# SCH_Stimulus-Shield-_GroeiAcademie-Frame.net
KiCad netlist of a schematic drawn in EasyEDA
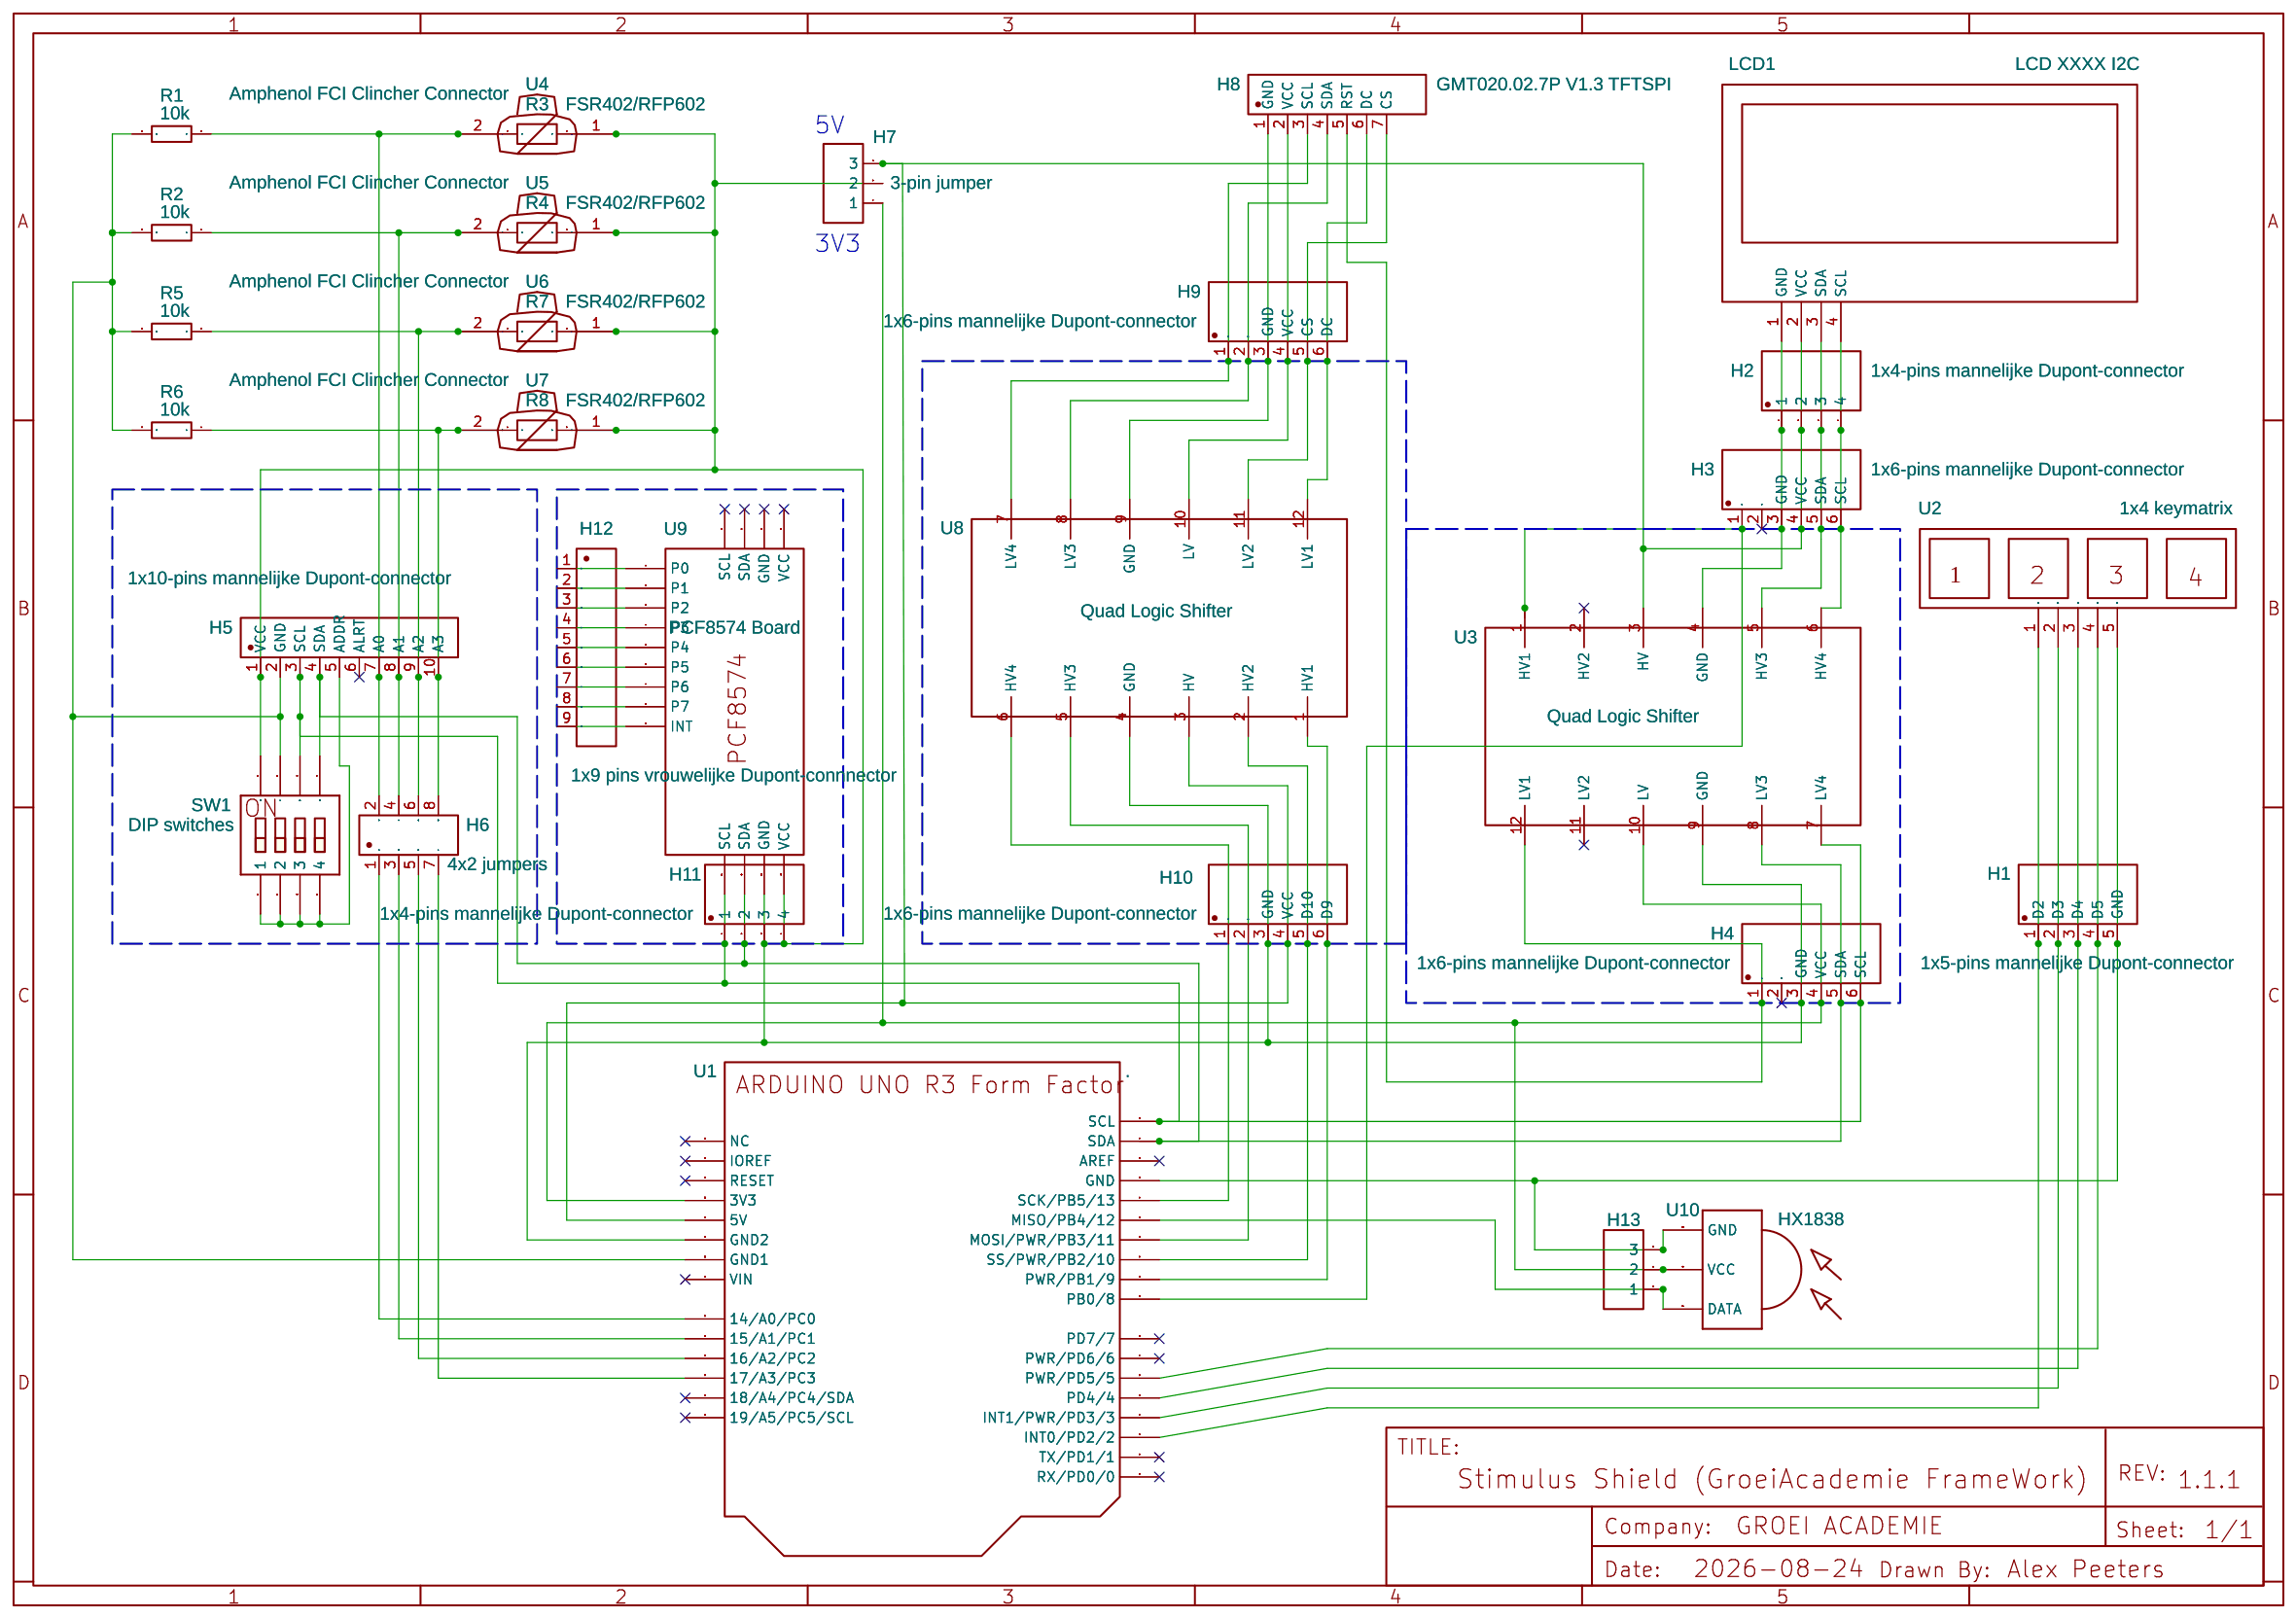
[diagram p0: schematic sheet]

(export (version "E")
  (design (tool "Eeschema 10.0.6"))
  (components
    (comp (ref "H1")
      (value "1x5-pins mannelijke Dupont-connector")
      (fields (field (name "Manufacturer Part") "B-2100S05P-A110") (field (name "Manufacturer") "Ckmtw(灿科盟)"))
      (libsource (lib "") (part "210S-1*5P L=11.6MMGold-plated black"))
    )
    (comp (ref "H2")
      (value "1x4-pins mannelijke Dupont-connector")
      (fields (field (name "Manufacturer Part") "B-2100S04P-A110") (field (name "Manufacturer") "Ckmtw(灿科盟)"))
      (libsource (lib "") (part "Header-Male-2.54_1x4"))
    )
    (comp (ref "H3")
      (value "1x6-pins mannelijke Dupont-connector")
      (fields (field (name "Manufacturer Part") "B-2100S06P-A110") (field (name "Manufacturer") "Ckmtw(灿科盟)"))
      (libsource (lib "") (part "210S-1*6P L=11.6MMGold-plated black"))
    )
    (comp (ref "H4")
      (value "1x6-pins mannelijke Dupont-connector")
      (fields (field (name "Manufacturer Part") "B-2100S06P-A110") (field (name "Manufacturer") "Ckmtw(灿科盟)"))
      (libsource (lib "") (part "210S-1*6P L=11.6MMGold-plated black"))
    )
    (comp (ref "H5")
      (value "1x10-pins mannelijke Dupont-connector")
      (fields (field (name "Manufacturer Part") "2.54-1*10") (field (name "Manufacturer") "ZHOURI(洲日)"))
      (libsource (lib "") (part "2.54-1*10"))
    )
    (comp (ref "H6")
      (value "4x2 jumpers")
      (fields (field (name "Manufacturer Part") "2.54-2*4P立贴针") (field (name "Manufacturer") "BOOMELE(博穆精密)"))
      (libsource (lib "") (part "2.54-2*4P立贴针"))
    )
    (comp (ref "H7") (value "3-pin jumper") (libsource (lib "") (part "HDR-F-2.54_1x3")))
    (comp (ref "H8")
      (value "GMT020.02.7P V1.3 TFTSPI")
      (fields (field (name "Manufacturer Part") "HDR-M-L12-3+4-1x8P-2.54"))
      (libsource (lib "") (part "PZ254R-11-08P"))
    )
    (comp (ref "H9")
      (value "1x6-pins mannelijke Dupont-connector")
      (fields (field (name "Manufacturer Part") "B-2100S06P-A110") (field (name "Manufacturer") "Ckmtw(灿科盟)"))
      (libsource (lib "") (part "210S-1*6P L=11.6MMGold-plated black_2"))
    )
    (comp (ref "H10")
      (value "1x6-pins mannelijke Dupont-connector")
      (fields (field (name "Manufacturer Part") "B-2100S06P-A110") (field (name "Manufacturer") "Ckmtw(灿科盟)"))
      (libsource (lib "") (part "210S-1*6P L=11.6MMGold-plated black_1"))
    )
    (comp (ref "H11")
      (value "1x4-pins mannelijke Dupont-connector")
      (fields (field (name "Manufacturer Part") "B-2100S04P-A110") (field (name "Manufacturer") "Ckmtw(灿科盟)"))
      (libsource (lib "") (part "Header-Male-2.54_1x4"))
    )
    (comp (ref "H12")
      (value "1x9 pins vrouwelijke Dupont-connnector")
      (fields
        (field (name "Manufacturer Part") "HX PM1.27-1x9P ZC H2.0")
        (field (name "Manufacturer") "hanxia(韩下)")
      )
      (libsource (lib "") (part "HX PM1.27-1X9P ZC H2.0"))
    )
    (comp (ref "H13") (value "HDR-M-2.54_1x3") (libsource (lib "") (part "HDR-M-2.54_1x3")))
    (comp (ref "LCD1") (value "LCD XXXX I2C") (libsource (lib "") (part "I2CLCD16X2_N")))
    (comp (ref "R1")
      (value "10k")
      (fields (field (name "Manufacturer") "Made in China"))
      (libsource (lib "") (part "330Ω (331) ±5%"))
    )
    (comp (ref "R2")
      (value "10k")
      (fields (field (name "Manufacturer") "Made in China"))
      (libsource (lib "") (part "330Ω (331) ±5%"))
    )
    (comp (ref "R3") (value "FSR402/RFP602") (libsource (lib "") (part "FSR402-OPCION1")))
    (comp (ref "R4") (value "FSR402/RFP602") (libsource (lib "") (part "FSR402-OPCION1")))
    (comp (ref "R5")
      (value "10k")
      (fields (field (name "Manufacturer") "Made in China"))
      (libsource (lib "") (part "330Ω (331) ±5%"))
    )
    (comp (ref "R6")
      (value "10k")
      (fields (field (name "Manufacturer") "Made in China"))
      (libsource (lib "") (part "330Ω (331) ±5%"))
    )
    (comp (ref "R7") (value "FSR402/RFP602") (libsource (lib "") (part "FSR402-OPCION1")))
    (comp (ref "R8") (value "FSR402/RFP602") (libsource (lib "") (part "FSR402-OPCION1")))
    (comp (ref "SW1")
      (value "DIP switches")
      (fields
        (field (name "Manufacturer Part") "DIP switch,Dip Switch,DSWB04LHGET")
        (field (name "Manufacturer") "KE")
      )
      (libsource (lib "") (part "DIP switch 4 Channel"))
    )
    (comp (ref "U1") (value ".") (libsource (lib "") (part "ARDUINO UNO r3")))
    (comp (ref "U2") (value "1x4 keymatrix") (libsource (lib "") (part "Клавиатура 4*4")))
    (comp (ref "U3") (value "Quad Logic Shifter") (libsource (lib "") (part "Quad Logic Shifter")))
    (comp (ref "U4")
      (value "Amphenol FCI Clincher Connector")
      (fields (field (name "Manufacturer Part") "AT04-2P-BM02") (field (name "Manufacturer") "Amphenol"))
      (libsource (lib "") (part "AT04-2P"))
    )
    (comp (ref "U5")
      (value "Amphenol FCI Clincher Connector")
      (fields (field (name "Manufacturer Part") "AT04-2P-BM02") (field (name "Manufacturer") "Amphenol"))
      (libsource (lib "") (part "AT04-2P"))
    )
    (comp (ref "U6")
      (value "Amphenol FCI Clincher Connector")
      (fields (field (name "Manufacturer Part") "AT04-2P-BM02") (field (name "Manufacturer") "Amphenol"))
      (libsource (lib "") (part "AT04-2P"))
    )
    (comp (ref "U7")
      (value "Amphenol FCI Clincher Connector")
      (fields (field (name "Manufacturer Part") "AT04-2P-BM02") (field (name "Manufacturer") "Amphenol"))
      (libsource (lib "") (part "AT04-2P"))
    )
    (comp (ref "U8") (value "Quad Logic Shifter") (libsource (lib "") (part "Quad Logic Shifter_1")))
    (comp (ref "U9")
      (value "PCF8574 Board")
      (fields
        (field (name "Manufacturer Part") "PCF8574 IO Expansion Board")
        (field (name "Manufacturer") "WaveShare")
      )
      (libsource (lib "") (part "PCF8574 IO Expansion Board"))
    )
    (comp (ref "U10") (value "HX1838") (libsource (lib "") (part "IR_HX1838")))
  )
  (nets
    (net (code "1") (name "Net-(H1-D2)") (class "Default")
      (node (ref "H1") (pin "1") (pinfunction "D2_1") (pintype "unspecified"))
      (node (ref "U1") (pin "3") (pinfunction "INT0/PD2/2_3") (pintype "unspecified"))
      (node (ref "U2") (pin "1") (pinfunction "C1_1") (pintype "unspecified"))
    )
    (net (code "2") (name "Net-(H1-D3)") (class "Default")
      (node (ref "H1") (pin "2") (pinfunction "D3_2") (pintype "unspecified"))
      (node (ref "U1") (pin "4") (pinfunction "INT1/PWR/PD3/3_4") (pintype "unspecified"))
      (node (ref "U2") (pin "2") (pinfunction "C2_2") (pintype "unspecified"))
    )
    (net (code "3") (name "Net-(H1-D4)") (class "Default")
      (node (ref "H1") (pin "3") (pinfunction "D4_3") (pintype "unspecified"))
      (node (ref "U1") (pin "5") (pinfunction "PD4/4_5") (pintype "unspecified"))
      (node (ref "U2") (pin "3") (pinfunction "C3_3") (pintype "unspecified"))
    )
    (net (code "4") (name "Net-(H1-D5)") (class "Default")
      (node (ref "H1") (pin "4") (pinfunction "D5_4") (pintype "unspecified"))
      (node (ref "U1") (pin "6") (pinfunction "PWR/PD5/5_6") (pintype "unspecified"))
      (node (ref "U2") (pin "4") (pinfunction "R1_4") (pintype "unspecified"))
    )
    (net (code "5") (name "Net-(H1-GND)") (class "Default")
      (node (ref "H1") (pin "5") (pinfunction "GND_5") (pintype "unspecified"))
      (node (ref "H13") (pin "3") (pinfunction "3_3") (pintype "input"))
      (node (ref "U1") (pin "15") (pinfunction "GND_15") (pintype "passive"))
      (node (ref "U10") (pin "GND") (pinfunction "GND_GND") (pintype "unspecified"))
      (node (ref "U2") (pin "5") (pinfunction "R2_5") (pintype "unspecified"))
    )
    (net (code "6") (name "Net-(H3-GND)") (class "Default")
      (node (ref "H2") (pin "1") (pinfunction "1_1") (pintype "unspecified"))
      (node (ref "H3") (pin "3") (pinfunction "GND_3") (pintype "unspecified"))
      (node (ref "LCD1") (pin "1") (pinfunction "GND_1") (pintype "unspecified"))
      (node (ref "U3") (pin "4") (pinfunction "GND_4") (pintype "unspecified"))
    )
    (net (code "7") (name "Net-(H3-SCL)") (class "Default")
      (node (ref "H2") (pin "4") (pinfunction "4_4") (pintype "unspecified"))
      (node (ref "H3") (pin "6") (pinfunction "SCL_6") (pintype "unspecified"))
      (node (ref "LCD1") (pin "4") (pinfunction "SCL_4") (pintype "unspecified"))
      (node (ref "U3") (pin "6") (pinfunction "HV4_6") (pintype "unspecified"))
    )
    (net (code "8") (name "Net-(H3-SDA)") (class "Default")
      (node (ref "H2") (pin "3") (pinfunction "3_3") (pintype "unspecified"))
      (node (ref "H3") (pin "5") (pinfunction "SDA_5") (pintype "unspecified"))
      (node (ref "LCD1") (pin "3") (pinfunction "SDA_3") (pintype "unspecified"))
      (node (ref "U3") (pin "5") (pinfunction "HV3_5") (pintype "unspecified"))
    )
    (net (code "9") (name "Net-(H4-SCL)") (class "Default")
      (node (ref "H11") (pin "1") (pinfunction "1_1") (pintype "unspecified"))
      (node (ref "H4") (pin "6") (pinfunction "SCL_6") (pintype "unspecified"))
      (node (ref "H5") (pin "3") (pinfunction "SCL_3") (pintype "unspecified"))
      (node (ref "SW1") (pin "3I") (pinfunction "6_3I") (pintype "input"))
      (node (ref "U1") (pin "18") (pinfunction "SCL_18") (pintype "unspecified"))
      (node (ref "U3") (pin "7") (pinfunction "LV4_7") (pintype "unspecified"))
      (node (ref "U9") (pin "SCL") (pinfunction "SCL_SCL") (pintype "unspecified"))
    )
    (net (code "10") (name "Net-(H4-SDA)") (class "Default")
      (node (ref "H11") (pin "2") (pinfunction "2_2") (pintype "unspecified"))
      (node (ref "H4") (pin "5") (pinfunction "SDA_5") (pintype "unspecified"))
      (node (ref "H5") (pin "4") (pinfunction "SDA_4") (pintype "unspecified"))
      (node (ref "SW1") (pin "4I") (pinfunction "5_4I") (pintype "input"))
      (node (ref "U1") (pin "17") (pinfunction "SDA_17") (pintype "unspecified"))
      (node (ref "U3") (pin "8") (pinfunction "LV3_8") (pintype "unspecified"))
      (node (ref "U9") (pin "SDA") (pinfunction "SDA_SDA") (pintype "unspecified"))
    )
    (net (code "11") (name "Net-(H4-VCC)") (class "Default")
      (node (ref "H13") (pin "2") (pinfunction "2_2") (pintype "input"))
      (node (ref "H4") (pin "4") (pinfunction "VCC_4") (pintype "unspecified"))
      (node (ref "H7") (pin "1") (pinfunction "1_1") (pintype "input"))
      (node (ref "U1") (pin "29") (pinfunction "3V3_29") (pintype "passive"))
      (node (ref "U10") (pin "VCC") (pinfunction "VCC_VCC") (pintype "unspecified"))
      (node (ref "U3") (pin "10") (pinfunction "LV_10") (pintype "unspecified"))
    )
    (net (code "12") (name "Net-(H5-A0)") (class "Default")
      (node (ref "H5") (pin "7") (pinfunction "A0_7") (pintype "unspecified"))
      (node (ref "H6") (pin "2") (pinfunction "2_2") (pintype "unspecified"))
      (node (ref "R1") (pin "1") (pinfunction "1_1") (pintype "unspecified"))
      (node (ref "R3") (pin "1") (pinfunction "1_1") (pintype "unspecified"))
      (node (ref "U4") (pin "2") (pinfunction "2_2") (pintype "unspecified"))
    )
    (net (code "13") (name "Net-(H5-A1)") (class "Default")
      (node (ref "H5") (pin "8") (pinfunction "A1_8") (pintype "unspecified"))
      (node (ref "H6") (pin "4") (pinfunction "4_4") (pintype "unspecified"))
      (node (ref "R2") (pin "1") (pinfunction "1_1") (pintype "unspecified"))
      (node (ref "R4") (pin "1") (pinfunction "1_1") (pintype "unspecified"))
      (node (ref "U5") (pin "2") (pinfunction "2_2") (pintype "unspecified"))
    )
    (net (code "14") (name "Net-(H5-A2)") (class "Default")
      (node (ref "H5") (pin "9") (pinfunction "A2_9") (pintype "unspecified"))
      (node (ref "H6") (pin "6") (pinfunction "6_6") (pintype "unspecified"))
      (node (ref "R5") (pin "1") (pinfunction "1_1") (pintype "unspecified"))
      (node (ref "R7") (pin "1") (pinfunction "1_1") (pintype "unspecified"))
      (node (ref "U6") (pin "2") (pinfunction "2_2") (pintype "unspecified"))
    )
    (net (code "15") (name "Net-(H5-A3)") (class "Default")
      (node (ref "H5") (pin "10") (pinfunction "A3_10") (pintype "unspecified"))
      (node (ref "H6") (pin "8") (pinfunction "8_8") (pintype "unspecified"))
      (node (ref "R6") (pin "1") (pinfunction "1_1") (pintype "unspecified"))
      (node (ref "R8") (pin "1") (pinfunction "1_1") (pintype "unspecified"))
      (node (ref "U7") (pin "2") (pinfunction "2_2") (pintype "unspecified"))
    )
    (net (code "16") (name "Net-(H5-ADDR)") (class "Default")
      (node (ref "H5") (pin "5") (pinfunction "ADDR_5") (pintype "unspecified"))
      (node (ref "SW1") (pin "1O") (pinfunction "1_1O") (pintype "input"))
      (node (ref "SW1") (pin "2O") (pinfunction "2_2O") (pintype "input"))
      (node (ref "SW1") (pin "3O") (pinfunction "3_3O") (pintype "input"))
      (node (ref "SW1") (pin "4O") (pinfunction "4_4O") (pintype "input"))
    )
    (net (code "17") (name "Net-(H5-GND)") (class "Default")
      (node (ref "H5") (pin "2") (pinfunction "GND_2") (pintype "unspecified"))
      (node (ref "R1") (pin "2") (pinfunction "2_2") (pintype "unspecified"))
      (node (ref "R2") (pin "2") (pinfunction "2_2") (pintype "unspecified"))
      (node (ref "R5") (pin "2") (pinfunction "2_2") (pintype "unspecified"))
      (node (ref "R6") (pin "2") (pinfunction "2_2") (pintype "unspecified"))
      (node (ref "SW1") (pin "2I") (pinfunction "7_2I") (pintype "input"))
      (node (ref "U1") (pin "26") (pinfunction "GND1_26") (pintype "passive"))
    )
    (net (code "18") (name "Net-(H5-VCC)") (class "Default")
      (node (ref "H11") (pin "4") (pinfunction "4_4") (pintype "unspecified"))
      (node (ref "H5") (pin "1") (pinfunction "VCC_1") (pintype "unspecified"))
      (node (ref "H7") (pin "2") (pinfunction "2_2") (pintype "input"))
      (node (ref "R3") (pin "2") (pinfunction "2_2") (pintype "unspecified"))
      (node (ref "R4") (pin "2") (pinfunction "2_2") (pintype "unspecified"))
      (node (ref "R7") (pin "2") (pinfunction "2_2") (pintype "unspecified"))
      (node (ref "R8") (pin "2") (pinfunction "2_2") (pintype "unspecified"))
      (node (ref "SW1") (pin "1I") (pinfunction "8_1I") (pintype "input"))
      (node (ref "U4") (pin "1") (pinfunction "1_1") (pintype "unspecified"))
      (node (ref "U5") (pin "1") (pinfunction "1_1") (pintype "unspecified"))
      (node (ref "U6") (pin "1") (pinfunction "1_1") (pintype "unspecified"))
      (node (ref "U7") (pin "1") (pinfunction "1_1") (pintype "unspecified"))
      (node (ref "U9") (pin "VCC") (pinfunction "VCC_VCC") (pintype "unspecified"))
    )
    (net (code "19") (name "Net-(H8-CS)") (class "Default")
      (node (ref "H8") (pin "7") (pinfunction "CS_7") (pintype "unspecified"))
      (node (ref "H9") (pin "5") (pinfunction "CS_5") (pintype "unspecified"))
      (node (ref "U8") (pin "11") (pinfunction "LV2_11") (pintype "unspecified"))
    )
    (net (code "20") (name "Net-(H8-DC)") (class "Default")
      (node (ref "H8") (pin "6") (pinfunction "DC_6") (pintype "unspecified"))
      (node (ref "H9") (pin "6") (pinfunction "DC_6") (pintype "unspecified"))
      (node (ref "U8") (pin "12") (pinfunction "LV1_12") (pintype "unspecified"))
    )
    (net (code "21") (name "Net-(H8-GND)") (class "Default")
      (node (ref "H8") (pin "1") (pinfunction "GND_1") (pintype "unspecified"))
      (node (ref "H9") (pin "3") (pinfunction "GND_3") (pintype "unspecified"))
      (node (ref "U8") (pin "9") (pinfunction "GND_9") (pintype "unspecified"))
    )
    (net (code "22") (name "Net-(H8-RST)") (class "Default")
      (node (ref "H4") (pin "1") (pinfunction "1_1") (pintype "unspecified"))
      (node (ref "H8") (pin "5") (pinfunction "RST_5") (pintype "unspecified"))
      (node (ref "U3") (pin "12") (pinfunction "LV1_12") (pintype "unspecified"))
    )
    (net (code "23") (name "Net-(H8-SCL)") (class "Default")
      (node (ref "H8") (pin "3") (pinfunction "SCL_3") (pintype "unspecified"))
      (node (ref "H9") (pin "1") (pinfunction "1_1") (pintype "unspecified"))
      (node (ref "U8") (pin "7") (pinfunction "LV4_7") (pintype "unspecified"))
    )
    (net (code "24") (name "Net-(H8-SDA)") (class "Default")
      (node (ref "H8") (pin "4") (pinfunction "SDA_4") (pintype "unspecified"))
      (node (ref "H9") (pin "2") (pinfunction "2_2") (pintype "unspecified"))
      (node (ref "U8") (pin "8") (pinfunction "LV3_8") (pintype "unspecified"))
    )
    (net (code "25") (name "Net-(H8-VCC)") (class "Default")
      (node (ref "H8") (pin "2") (pinfunction "VCC_2") (pintype "unspecified"))
      (node (ref "H9") (pin "4") (pinfunction "VCC_4") (pintype "unspecified"))
      (node (ref "U8") (pin "10") (pinfunction "LV_10") (pintype "unspecified"))
    )
    (net (code "26") (name "Net-(H10-D9)") (class "Default")
      (node (ref "H10") (pin "6") (pinfunction "D9_6") (pintype "unspecified"))
      (node (ref "U1") (pin "10") (pinfunction "PWR/PB1/9_10") (pintype "unspecified"))
      (node (ref "U8") (pin "1") (pinfunction "HV1_1") (pintype "unspecified"))
    )
    (net (code "27") (name "Net-(H10-D10)") (class "Default")
      (node (ref "H10") (pin "5") (pinfunction "D10_5") (pintype "unspecified"))
      (node (ref "U1") (pin "11") (pinfunction "SS/PWR/PB2/10_11") (pintype "unspecified"))
      (node (ref "U8") (pin "2") (pinfunction "HV2_2") (pintype "unspecified"))
    )
    (net (code "28") (name "Net-(H10-GND)") (class "Default")
      (node (ref "H10") (pin "3") (pinfunction "GND_3") (pintype "unspecified"))
      (node (ref "H11") (pin "3") (pinfunction "3_3") (pintype "unspecified"))
      (node (ref "H4") (pin "3") (pinfunction "GND_3") (pintype "unspecified"))
      (node (ref "U1") (pin "27") (pinfunction "GND2_27") (pintype "passive"))
      (node (ref "U3") (pin "9") (pinfunction "GND_9") (pintype "unspecified"))
      (node (ref "U8") (pin "4") (pinfunction "GND_4") (pintype "unspecified"))
      (node (ref "U9") (pin "GND") (pinfunction "GND_GND") (pintype "unspecified"))
    )
    (net (code "29") (name "Net-(H10-VCC)") (class "Default")
      (node (ref "H10") (pin "4") (pinfunction "VCC_4") (pintype "unspecified"))
      (node (ref "H2") (pin "2") (pinfunction "2_2") (pintype "unspecified"))
      (node (ref "H3") (pin "4") (pinfunction "VCC_4") (pintype "unspecified"))
      (node (ref "H7") (pin "3") (pinfunction "3_3") (pintype "input"))
      (node (ref "LCD1") (pin "2") (pinfunction "VCC_2") (pintype "unspecified"))
      (node (ref "U1") (pin "28") (pinfunction "5V_28") (pintype "passive"))
      (node (ref "U3") (pin "3") (pinfunction "HV_3") (pintype "unspecified"))
      (node (ref "U8") (pin "3") (pinfunction "HV_3") (pintype "unspecified"))
    )
    (net (code "30") (name "Net-(U1-14{slash}A0{slash}PC0)") (class "Default")
      (node (ref "H6") (pin "1") (pinfunction "1_1") (pintype "unspecified"))
      (node (ref "U1") (pin "24") (pinfunction "14/A0/PC0_24") (pintype "unspecified"))
    )
    (net (code "31") (name "Net-(U1-15{slash}A1{slash}PC1)") (class "Default")
      (node (ref "H6") (pin "3") (pinfunction "3_3") (pintype "unspecified"))
      (node (ref "U1") (pin "23") (pinfunction "15/A1/PC1_23") (pintype "unspecified"))
    )
    (net (code "32") (name "Net-(U1-16{slash}A2{slash}PC2)") (class "Default")
      (node (ref "H6") (pin "5") (pinfunction "5_5") (pintype "unspecified"))
      (node (ref "U1") (pin "22") (pinfunction "16/A2/PC2_22") (pintype "unspecified"))
    )
    (net (code "33") (name "Net-(U1-17{slash}A3{slash}PC3)") (class "Default")
      (node (ref "H6") (pin "7") (pinfunction "7_7") (pintype "unspecified"))
      (node (ref "U1") (pin "21") (pinfunction "17/A3/PC3_21") (pintype "unspecified"))
    )
    (net (code "34") (name "Net-(U1-MISO{slash}PB4{slash}12)") (class "Default")
      (node (ref "H13") (pin "1") (pinfunction "1_1") (pintype "input"))
      (node (ref "U1") (pin "13") (pinfunction "MISO/PB4/12_13") (pintype "unspecified"))
      (node (ref "U10") (pin "DATA") (pinfunction "DATA_DATA") (pintype "unspecified"))
    )
    (net (code "35") (name "Net-(U1-MOSI{slash}PWR{slash}PB3{slash}11)") (class "Default")
      (node (ref "H10") (pin "2") (pinfunction "2_2") (pintype "unspecified"))
      (node (ref "U1") (pin "12") (pinfunction "MOSI/PWR/PB3/11_12") (pintype "unspecified"))
    )
    (net (code "36") (name "Net-(U1-PB0{slash}8)") (class "Default")
      (node (ref "H3") (pin "1") (pinfunction "1_1") (pintype "unspecified"))
      (node (ref "U1") (pin "9") (pinfunction "PB0/8_9") (pintype "unspecified"))
      (node (ref "U3") (pin "1") (pinfunction "HV1_1") (pintype "unspecified"))
    )
    (net (code "37") (name "Net-(U1-SCK{slash}PB5{slash}13)") (class "Default")
      (node (ref "H10") (pin "1") (pinfunction "1_1") (pintype "unspecified"))
      (node (ref "U1") (pin "14") (pinfunction "SCK/PB5/13_14") (pintype "unspecified"))
    )
    (net (code "38") (name "Net-(U9-INT)") (class "Default")
      (node (ref "H12") (pin "9") (pinfunction "9_9") (pintype "unspecified"))
      (node (ref "U9") (pin "9") (pinfunction "INT_9") (pintype "unspecified"))
    )
    (net (code "39") (name "Net-(U9-P0)") (class "Default")
      (node (ref "H12") (pin "1") (pinfunction "1_1") (pintype "unspecified"))
      (node (ref "U9") (pin "1") (pinfunction "P0_1") (pintype "unspecified"))
    )
    (net (code "40") (name "Net-(U9-P1)") (class "Default")
      (node (ref "H12") (pin "2") (pinfunction "2_2") (pintype "unspecified"))
      (node (ref "U9") (pin "2") (pinfunction "P1_2") (pintype "unspecified"))
    )
    (net (code "41") (name "Net-(U9-P2)") (class "Default")
      (node (ref "H12") (pin "3") (pinfunction "3_3") (pintype "unspecified"))
      (node (ref "U9") (pin "3") (pinfunction "P2_3") (pintype "unspecified"))
    )
    (net (code "42") (name "Net-(U9-P3)") (class "Default")
      (node (ref "H12") (pin "4") (pinfunction "4_4") (pintype "unspecified"))
      (node (ref "U9") (pin "4") (pinfunction "P3_4") (pintype "unspecified"))
    )
    (net (code "43") (name "Net-(U9-P4)") (class "Default")
      (node (ref "H12") (pin "5") (pinfunction "5_5") (pintype "unspecified"))
      (node (ref "U9") (pin "5") (pinfunction "P4_5") (pintype "unspecified"))
    )
    (net (code "44") (name "Net-(U9-P5)") (class "Default")
      (node (ref "H12") (pin "6") (pinfunction "6_6") (pintype "unspecified"))
      (node (ref "U9") (pin "6") (pinfunction "P5_6") (pintype "unspecified"))
    )
    (net (code "45") (name "Net-(U9-P6)") (class "Default")
      (node (ref "H12") (pin "7") (pinfunction "7_7") (pintype "unspecified"))
      (node (ref "U9") (pin "7") (pinfunction "P6_7") (pintype "unspecified"))
    )
    (net (code "46") (name "Net-(U9-P7)") (class "Default")
      (node (ref "H12") (pin "8") (pinfunction "8_8") (pintype "unspecified"))
      (node (ref "U9") (pin "8") (pinfunction "P7_8") (pintype "unspecified"))
    )
    (net (code "47") (name "unconnected-(H3-Pad2)") (class "Default")
      (node (ref "H3") (pin "2") (pinfunction "2_2") (pintype "unspecified+no_connect"))
    )
    (net (code "48") (name "unconnected-(H4-Pad2)") (class "Default")
      (node (ref "H4") (pin "2") (pinfunction "2_2") (pintype "unspecified+no_connect"))
    )
    (net (code "49") (name "unconnected-(H5-ALRT-Pad6)") (class "Default")
      (node (ref "H5") (pin "6") (pinfunction "ALRT_6") (pintype "unspecified+no_connect"))
    )
    (net (code "50") (name "unconnected-(U1-18{slash}A4{slash}PC4{slash}SDA-Pad20)") (class "Default")
      (node (ref "U1") (pin "20") (pinfunction "18/A4/PC4/SDA_20") (pintype "unspecified+no_connect"))
    )
    (net (code "51") (name "unconnected-(U1-19{slash}A5{slash}PC5{slash}SCL-Pad19)") (class "Default")
      (node (ref "U1") (pin "19") (pinfunction "19/A5/PC5/SCL_19") (pintype "unspecified+no_connect"))
    )
    (net (code "52") (name "unconnected-(U1-AREF-Pad16)") (class "Default")
      (node (ref "U1") (pin "16") (pinfunction "AREF_16") (pintype "unspecified+no_connect"))
    )
    (net (code "53") (name "unconnected-(U1-IOREF-Pad31)") (class "Default")
      (node (ref "U1") (pin "31") (pinfunction "IOREF_31") (pintype "unspecified+no_connect"))
    )
    (net (code "54") (name "unconnected-(U1-NC-Pad32)") (class "Default")
      (node (ref "U1") (pin "32") (pinfunction "NC_32") (pintype "unspecified+no_connect"))
    )
    (net (code "55") (name "unconnected-(U1-PD7{slash}7-Pad8)") (class "Default")
      (node (ref "U1") (pin "8") (pinfunction "PD7/7_8") (pintype "unspecified+no_connect"))
    )
    (net (code "56") (name "unconnected-(U1-PWR{slash}PD6{slash}6-Pad7)") (class "Default")
      (node (ref "U1") (pin "7") (pinfunction "PWR/PD6/6_7") (pintype "unspecified+no_connect"))
    )
    (net (code "57") (name "unconnected-(U1-RESET-Pad30)") (class "Default")
      (node (ref "U1") (pin "30") (pinfunction "RESET_30") (pintype "unspecified+no_connect"))
    )
    (net (code "58") (name "unconnected-(U1-RX{slash}PD0{slash}0-Pad1)") (class "Default")
      (node (ref "U1") (pin "1") (pinfunction "RX/PD0/0_1") (pintype "unspecified+no_connect"))
    )
    (net (code "59") (name "unconnected-(U1-TX{slash}PD1{slash}1-Pad2)") (class "Default")
      (node (ref "U1") (pin "2") (pinfunction "TX/PD1/1_2") (pintype "unspecified+no_connect"))
    )
    (net (code "60") (name "unconnected-(U1-VIN-Pad25)") (class "Default")
      (node (ref "U1") (pin "25") (pinfunction "VIN_25") (pintype "passive+no_connect"))
    )
    (net (code "61") (name "unconnected-(U3-HV2-Pad2)") (class "Default")
      (node (ref "U3") (pin "2") (pinfunction "HV2_2") (pintype "unspecified+no_connect"))
    )
    (net (code "62") (name "unconnected-(U3-LV2-Pad11)") (class "Default")
      (node (ref "U3") (pin "11") (pinfunction "LV2_11") (pintype "unspecified+no_connect"))
    )
    (net (code "63") (name "unconnected-(U8-HV3-Pad5)") (class "Default")
      (node (ref "U8") (pin "5") (pinfunction "HV3_5") (pintype "unspecified"))
    )
    (net (code "64") (name "unconnected-(U8-HV4-Pad6)") (class "Default")
      (node (ref "U8") (pin "6") (pinfunction "HV4_6") (pintype "unspecified"))
    )
    (net (code "65") (name "unconnected-(U9-GND-Pad12)") (class "Default")
      (node (ref "U9") (pin "12") (pinfunction "GND_12") (pintype "unspecified+no_connect"))
    )
    (net (code "66") (name "unconnected-(U9-SCL-Pad10)") (class "Default")
      (node (ref "U9") (pin "10") (pinfunction "SCL_10") (pintype "unspecified+no_connect"))
    )
    (net (code "67") (name "unconnected-(U9-SDA-Pad11)") (class "Default")
      (node (ref "U9") (pin "11") (pinfunction "SDA_11") (pintype "unspecified+no_connect"))
    )
    (net (code "68") (name "unconnected-(U9-VCC-Pad13)") (class "Default")
      (node (ref "U9") (pin "13") (pinfunction "VCC_13") (pintype "unspecified+no_connect"))
    )
  )
)
